# power1.net
KiCad netlist of a schematic drawn in Altium Designer
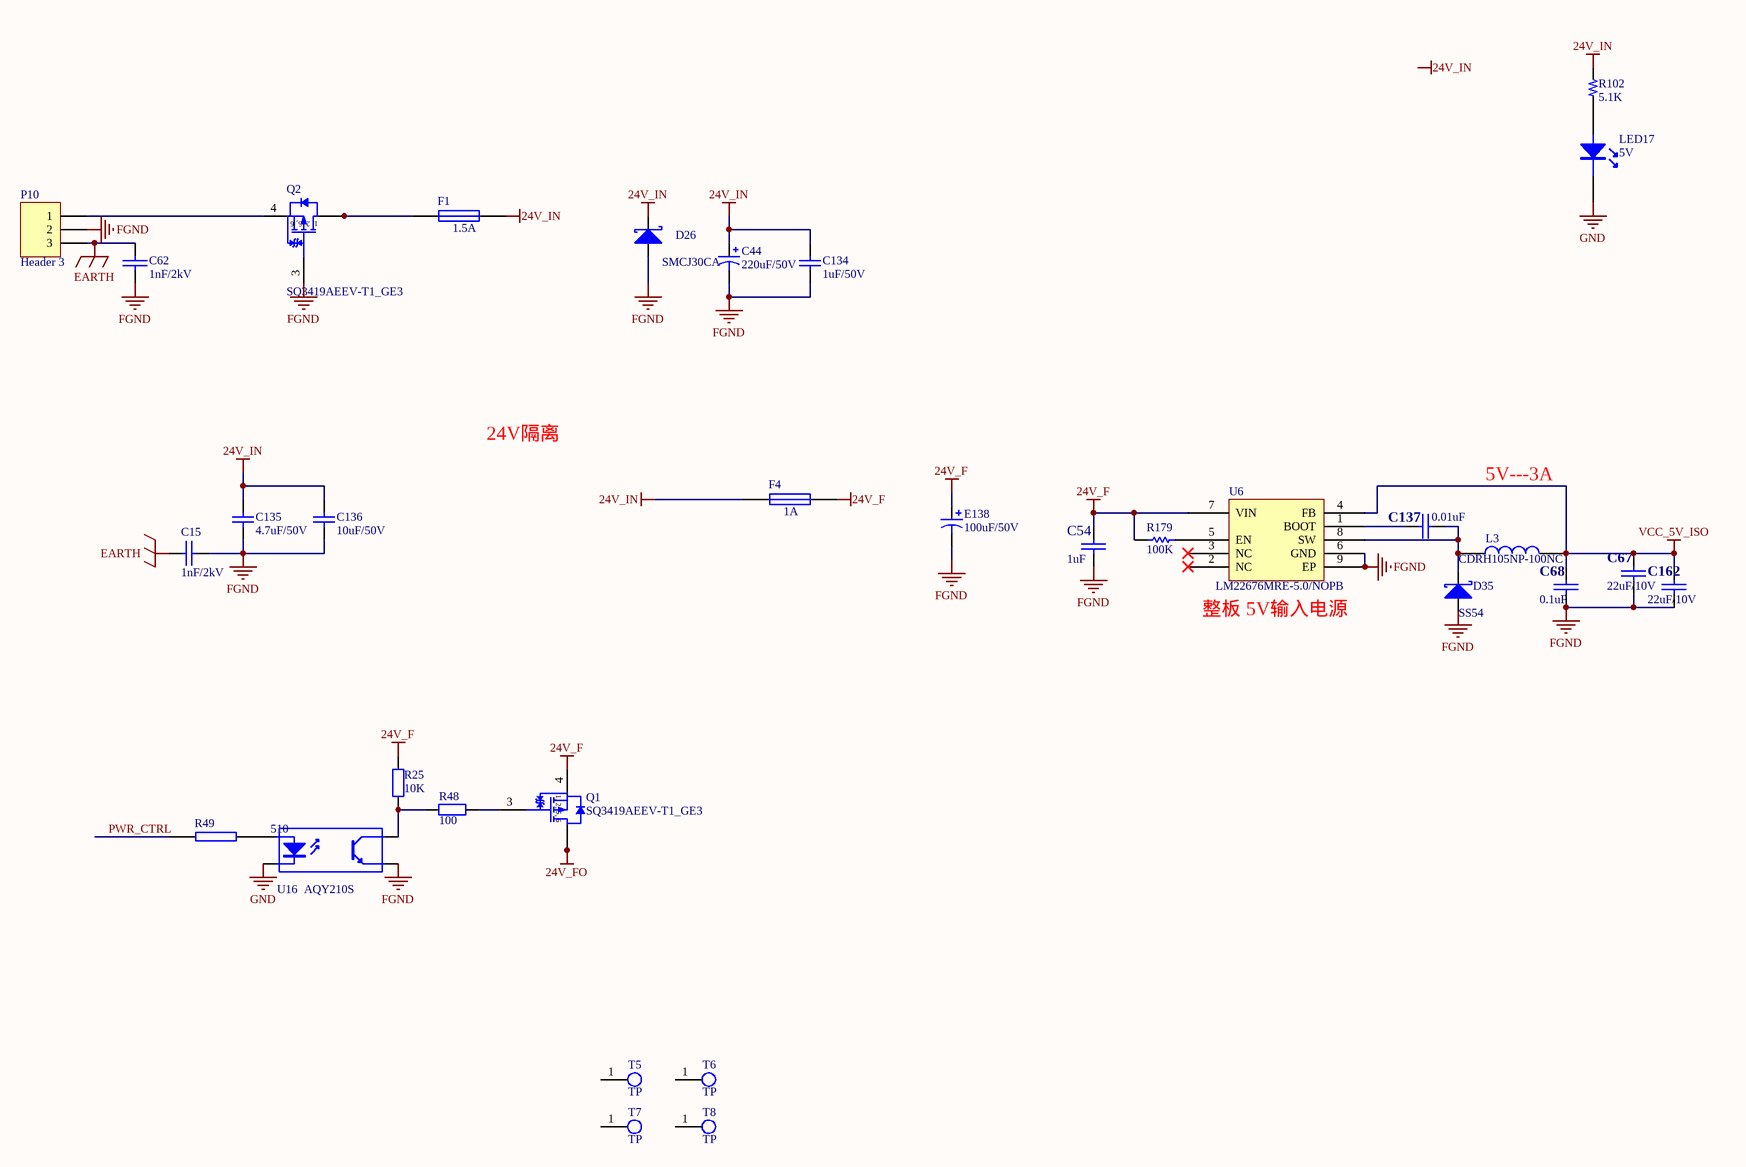
[diagram p0: power1.SchDoc]

(export (version "E")
  (design (tool "Eeschema 10.0.6"))
  (components
    (comp (ref "C15")
      (value "1nF/2kV")
      (footprint "1206C")
      (description "Capacitor")
      (libsource (lib "*") (part "CAP"))
    )
    (comp (ref "C44")
      (value "220uF/50V")
      (footprint "Φ10×10")
      (description "Polarized Capacitor (Radial)")
      (fields (field (name "PUBLISHER") "Altium Limited"))
      (libsource (lib "Miscellaneous Devices") (part "Cap Pol1"))
    )
    (comp (ref "C54")
      (value "1uF")
      (footprint "0603C")
      (description "Capacitor")
      (libsource (lib "*") (part "CAP"))
    )
    (comp (ref "C62")
      (value "1nF/2kV")
      (footprint "1206C")
      (description "Capacitor")
      (libsource (lib "*") (part "CAP"))
    )
    (comp (ref "C67")
      (value "22uF/10V")
      (footprint "1210C")
      (description "Capacitor")
      (libsource (lib "*") (part "CAP"))
    )
    (comp (ref "C68")
      (value "0.1uF")
      (footprint "0603C")
      (description "Capacitor")
      (libsource (lib "*") (part "CAP"))
    )
    (comp (ref "C134")
      (value "1uF/50V")
      (footprint "1210C")
      (description "Capacitor")
      (fields (field (name "PUBLISHER") "Altium Limited"))
      (libsource (lib "Miscellaneous Devices") (part "Cap"))
    )
    (comp (ref "C135")
      (value "4.7uF/50V")
      (footprint "1210C")
      (description "Capacitor")
      (fields (field (name "PUBLISHER") "Altium Limited"))
      (libsource (lib "Miscellaneous Devices") (part "Cap"))
    )
    (comp (ref "C136")
      (value "10uF/50V")
      (footprint "1210C")
      (description "Capacitor")
      (fields (field (name "PUBLISHER") "Altium Limited"))
      (libsource (lib "Miscellaneous Devices") (part "Cap"))
    )
    (comp (ref "C137")
      (value "0.01uF")
      (footprint "0603C")
      (description "Capacitor")
      (libsource (lib "*") (part "CAP"))
    )
    (comp (ref "C162")
      (value "22uF/10V")
      (footprint "1210C")
      (description "Capacitor")
      (libsource (lib "*") (part "CAP"))
    )
    (comp (ref "D26")
      (value "SMCJ30CA")
      (footprint "SMC")
      (description "Schottky Diode")
      (libsource (lib "*") (part "DIODE S"))
    )
    (comp (ref "D35")
      (value "SS54")
      (footprint "SMC")
      (description "Schottky Diode")
      (libsource (lib "*") (part "DIODE S"))
    )
    (comp (ref "E138")
      (value "100uF/50V")
      (footprint "Φ10×10")
      (description "Polarized Capacitor (Radial)")
      (fields (field (name "PUBLISHER") "Altium Limited"))
      (libsource (lib "Miscellaneous Devices") (part "Cap Pol1"))
    )
    (comp (ref "F1")
      (value "1.5A")
      (footprint "1812-F")
      (description "Fuse")
      (fields (field (name "PUBLISHER") "Altium Limited"))
      (libsource (lib "Miscellaneous Devices") (part "Fuse 1"))
    )
    (comp (ref "F4")
      (value "1A")
      (footprint "1812-F")
      (description "Fuse")
      (fields (field (name "PUBLISHER") "Altium Limited"))
      (libsource (lib "Miscellaneous Devices") (part "Fuse 1"))
    )
    (comp (ref "L3") (value "CDRH105NP-100NC") (footprint "CDRH105") (libsource (lib "*") (part "INDUCTOR")))
    (comp (ref "LED17") (value "5V") (footprint "0603LED") (libsource (lib "*") (part "LED")))
    (comp (ref "P10")
      (value "Header 3")
      (footprint "2ETYR-5.08-03P-14-100")
      (description "Header, 3-Pin")
      (fields (field (name "PUBLISHER") "Altium Limited"))
      (libsource (lib "Miscellaneous Connectors") (part "Header 3"))
    )
    (comp (ref "Q1")
      (value "SQ3419AEEV-T1_GE3")
      (footprint "VISH-TSOP-6_V")
      (description "Automotive P-Channel MOSFET, 6.9 A, 40 V, -55 to 175 degC, 6-Pin TSOP, RoHS, Tape and Reel")
      (fields (field (name "MANUFACTURER") "International Rectifier"))
      (libsource (lib "Bogen") (part "SQ3419AEEV-T1_GE3"))
    )
    (comp (ref "Q2")
      (value "SQ3419AEEV-T1_GE3")
      (footprint "VISH-TSOP-6_V")
      (description "Automotive P-Channel MOSFET, 6.9 A, 40 V, -55 to 175 degC, 6-Pin TSOP, RoHS, Tape and Reel")
      (fields (field (name "MANUFACTURER") "International Rectifier"))
      (libsource (lib "Bogen") (part "SQ3419AEEV-T1_GE3"))
    )
    (comp (ref "R25") (value "10K") (footprint "0603R") (libsource (lib "MQlibrary") (part "Res0805M")))
    (comp (ref "R48") (value "100") (footprint "0603R") (libsource (lib "") (part "Res0805M_1")))
    (comp (ref "R49") (value "510") (footprint "0603R") (libsource (lib "*") (part "RES2")))
    (comp (ref "R102")
      (value "5.1K")
      (footprint "0603R")
      (description "R")
      (libsource (lib "JRJ_1") (part "R"))
    )
    (comp (ref "R179")
      (value "100K")
      (footprint "0603R")
      (description "Resistor")
      (fields (field (name "PUBLISHER") "Altium Limited"))
      (libsource (lib "Miscellaneous Devices") (part "Res1"))
    )
    (comp (ref "T5") (value "TP") (footprint "m2.5") (libsource (lib "Schlib_20110825") (part "TP")))
    (comp (ref "T6") (value "TP") (footprint "m2.5") (libsource (lib "Schlib_20110825") (part "TP")))
    (comp (ref "T7") (value "TP") (footprint "m2.5") (libsource (lib "Schlib_20110825") (part "TP")))
    (comp (ref "T8") (value "TP") (footprint "m2.5") (libsource (lib "Schlib_20110825") (part "TP")))
    (comp (ref "U6")
      (value "LM22676MRE-5.0/NOPB")
      (footprint "SOP127P600X168_HS-8N")
      (libsource (lib "Schlib1") (part "LM22676MR-5.0"))
    )
    (comp (ref "U16")
      (value "AQY210S")
      (footprint "sop4")
      (description "4-Pin Phototransistor Optocoupler")
      (fields (field (name "PUBLISHER") "Altium Limited"))
      (libsource (lib "Miscellaneous Devices") (part "Optoisolator1"))
    )
  )
  (nets
    (net (code "1") (name "/PWR_CTRL") (class "Default")
      (node (ref "R49") (pin "2") (pinfunction "2_2") (pintype "passive"))
    )
    (net (code "2") (name "24V_F") (class "Default")
      (node (ref "C54") (pin "2") (pinfunction "2_2") (pintype "passive"))
      (node (ref "E138") (pin "1") (pinfunction "1_1") (pintype "passive"))
      (node (ref "F4") (pin "2") (pinfunction "2_2") (pintype "passive"))
      (node (ref "Q1") (pin "4") (pinfunction "S_4") (pintype "passive"))
      (node (ref "R179") (pin "2") (pinfunction "2_2") (pintype "passive"))
      (node (ref "R25") (pin "2") (pinfunction "2_2") (pintype "passive"))
      (node (ref "U6") (pin "7") (pinfunction "VIN_7") (pintype "passive"))
    )
    (net (code "3") (name "24V_FO") (class "Default")
      (node (ref "Q1") (pin "1") (pinfunction "D_1") (pintype "passive"))
      (node (ref "Q1") (pin "2") (pinfunction "D_2") (pintype "passive"))
      (node (ref "Q1") (pin "5") (pinfunction "D_5") (pintype "passive"))
      (node (ref "Q1") (pin "6") (pinfunction "D_6") (pintype "passive"))
    )
    (net (code "4") (name "24V_IN") (class "Default")
      (node (ref "C134") (pin "2") (pinfunction "2_2") (pintype "passive"))
      (node (ref "C135") (pin "2") (pinfunction "2_2") (pintype "passive"))
      (node (ref "C136") (pin "2") (pinfunction "2_2") (pintype "passive"))
      (node (ref "C44") (pin "1") (pinfunction "1_1") (pintype "passive"))
      (node (ref "D26") (pin "2") (pinfunction "K_2") (pintype "passive"))
      (node (ref "F1") (pin "2") (pinfunction "2_2") (pintype "passive"))
      (node (ref "F4") (pin "1") (pinfunction "1_1") (pintype "passive"))
      (node (ref "R102") (pin "2") (pintype "passive"))
    )
    (net (code "5") (name "EARTH") (class "Default")
      (node (ref "C15") (pin "2") (pinfunction "2_2") (pintype "passive"))
      (node (ref "C62") (pin "2") (pinfunction "2_2") (pintype "passive"))
      (node (ref "P10") (pin "3") (pinfunction "3_3") (pintype "passive"))
    )
    (net (code "6") (name "FGND") (class "Default")
      (node (ref "C134") (pin "1") (pinfunction "1_1") (pintype "passive"))
      (node (ref "C135") (pin "1") (pinfunction "1_1") (pintype "passive"))
      (node (ref "C136") (pin "1") (pinfunction "1_1") (pintype "passive"))
      (node (ref "C15") (pin "1") (pinfunction "1_1") (pintype "passive"))
      (node (ref "C162") (pin "2") (pinfunction "2_2") (pintype "passive"))
      (node (ref "C44") (pin "2") (pinfunction "2_2") (pintype "passive"))
      (node (ref "C54") (pin "1") (pinfunction "1_1") (pintype "passive"))
      (node (ref "C62") (pin "1") (pinfunction "1_1") (pintype "passive"))
      (node (ref "C67") (pin "2") (pinfunction "2_2") (pintype "passive"))
      (node (ref "C68") (pin "2") (pinfunction "2_2") (pintype "passive"))
      (node (ref "D26") (pin "1") (pinfunction "A_1") (pintype "passive"))
      (node (ref "D35") (pin "1") (pinfunction "A_1") (pintype "passive"))
      (node (ref "E138") (pin "2") (pinfunction "2_2") (pintype "passive"))
      (node (ref "P10") (pin "2") (pinfunction "2_2") (pintype "passive"))
      (node (ref "Q2") (pin "3") (pinfunction "G_3") (pintype "passive"))
      (node (ref "U16") (pin "3") (pinfunction "E_3") (pintype "passive"))
      (node (ref "U6") (pin "6") (pinfunction "GND_6") (pintype "passive"))
      (node (ref "U6") (pin "9") (pinfunction "EP_9") (pintype "passive"))
    )
    (net (code "7") (name "GND") (class "Default")
      (node (ref "LED17") (pin "2") (pinfunction "2_2") (pintype "passive"))
      (node (ref "U16") (pin "2") (pinfunction "K_2") (pintype "passive"))
    )
    (net (code "8") (name "Net-(D35-K)") (class "Default")
      (node (ref "C137") (pin "1") (pinfunction "1_1") (pintype "passive"))
      (node (ref "D35") (pin "2") (pinfunction "K_2") (pintype "passive"))
      (node (ref "L3") (pin "1") (pinfunction "1_1") (pintype "passive"))
      (node (ref "U6") (pin "8") (pinfunction "SW_8") (pintype "passive"))
    )
    (net (code "9") (name "Net-(F1-Pad1)") (class "Default")
      (node (ref "F1") (pin "1") (pinfunction "1_1") (pintype "passive"))
      (node (ref "Q2") (pin "1") (pinfunction "D_1") (pintype "passive"))
      (node (ref "Q2") (pin "2") (pinfunction "D_2") (pintype "passive"))
      (node (ref "Q2") (pin "5") (pinfunction "D_5") (pintype "passive"))
      (node (ref "Q2") (pin "6") (pinfunction "D_6") (pintype "passive"))
    )
    (net (code "10") (name "Net-(LED17-Pad1)") (class "Default")
      (node (ref "LED17") (pin "1") (pinfunction "1_1") (pintype "passive"))
      (node (ref "R102") (pin "1") (pintype "passive"))
    )
    (net (code "11") (name "Net-(Q1-G)") (class "Default")
      (node (ref "Q1") (pin "3") (pinfunction "G_3") (pintype "passive"))
      (node (ref "R48") (pin "1") (pinfunction "1_1") (pintype "passive"))
    )
    (net (code "12") (name "Net-(Q2-S)") (class "Default")
      (node (ref "P10") (pin "1") (pinfunction "1_1") (pintype "passive"))
      (node (ref "Q2") (pin "4") (pinfunction "S_4") (pintype "passive"))
    )
    (net (code "13") (name "Net-(U6-BOOT)") (class "Default")
      (node (ref "C137") (pin "2") (pinfunction "2_2") (pintype "passive"))
      (node (ref "U6") (pin "1") (pinfunction "BOOT_1") (pintype "passive"))
    )
    (net (code "14") (name "Net-(U6-EN)") (class "Default")
      (node (ref "R179") (pin "1") (pinfunction "1_1") (pintype "passive"))
      (node (ref "U6") (pin "5") (pinfunction "EN_5") (pintype "passive"))
    )
    (net (code "15") (name "Net-(U16-A)") (class "Default")
      (node (ref "R49") (pin "1") (pinfunction "1_1") (pintype "passive"))
      (node (ref "U16") (pin "1") (pinfunction "A_1") (pintype "passive"))
    )
    (net (code "16") (name "Net-(U16-C)") (class "Default")
      (node (ref "R25") (pin "1") (pinfunction "1_1") (pintype "passive"))
      (node (ref "R48") (pin "2") (pinfunction "2_2") (pintype "passive"))
      (node (ref "U16") (pin "4") (pinfunction "C_4") (pintype "passive"))
    )
    (net (code "17") (name "VCC_5V_ISO") (class "Default")
      (node (ref "C162") (pin "1") (pinfunction "1_1") (pintype "passive"))
      (node (ref "C67") (pin "1") (pinfunction "1_1") (pintype "passive"))
      (node (ref "C68") (pin "1") (pinfunction "1_1") (pintype "passive"))
      (node (ref "L3") (pin "2") (pinfunction "2_2") (pintype "passive"))
      (node (ref "U6") (pin "4") (pinfunction "FB_4") (pintype "passive"))
    )
    (net (code "18") (name "unconnected-(T5-Pad1)") (class "Default")
      (node (ref "T5") (pin "1") (pintype "passive"))
    )
    (net (code "19") (name "unconnected-(T6-Pad1)") (class "Default")
      (node (ref "T6") (pin "1") (pintype "passive"))
    )
    (net (code "20") (name "unconnected-(T7-Pad1)") (class "Default")
      (node (ref "T7") (pin "1") (pintype "passive"))
    )
    (net (code "21") (name "unconnected-(T8-Pad1)") (class "Default")
      (node (ref "T8") (pin "1") (pintype "passive"))
    )
    (net (code "22") (name "unconnected-(U6-NC-Pad2)") (class "Default")
      (node (ref "U6") (pin "2") (pinfunction "NC_2") (pintype "passive+no_connect"))
    )
    (net (code "23") (name "unconnected-(U6-NC-Pad3)") (class "Default")
      (node (ref "U6") (pin "3") (pinfunction "NC_3") (pintype "passive+no_connect"))
    )
  )
)
